# Audio.net
KiCad netlist of a schematic drawn in Altium Designer
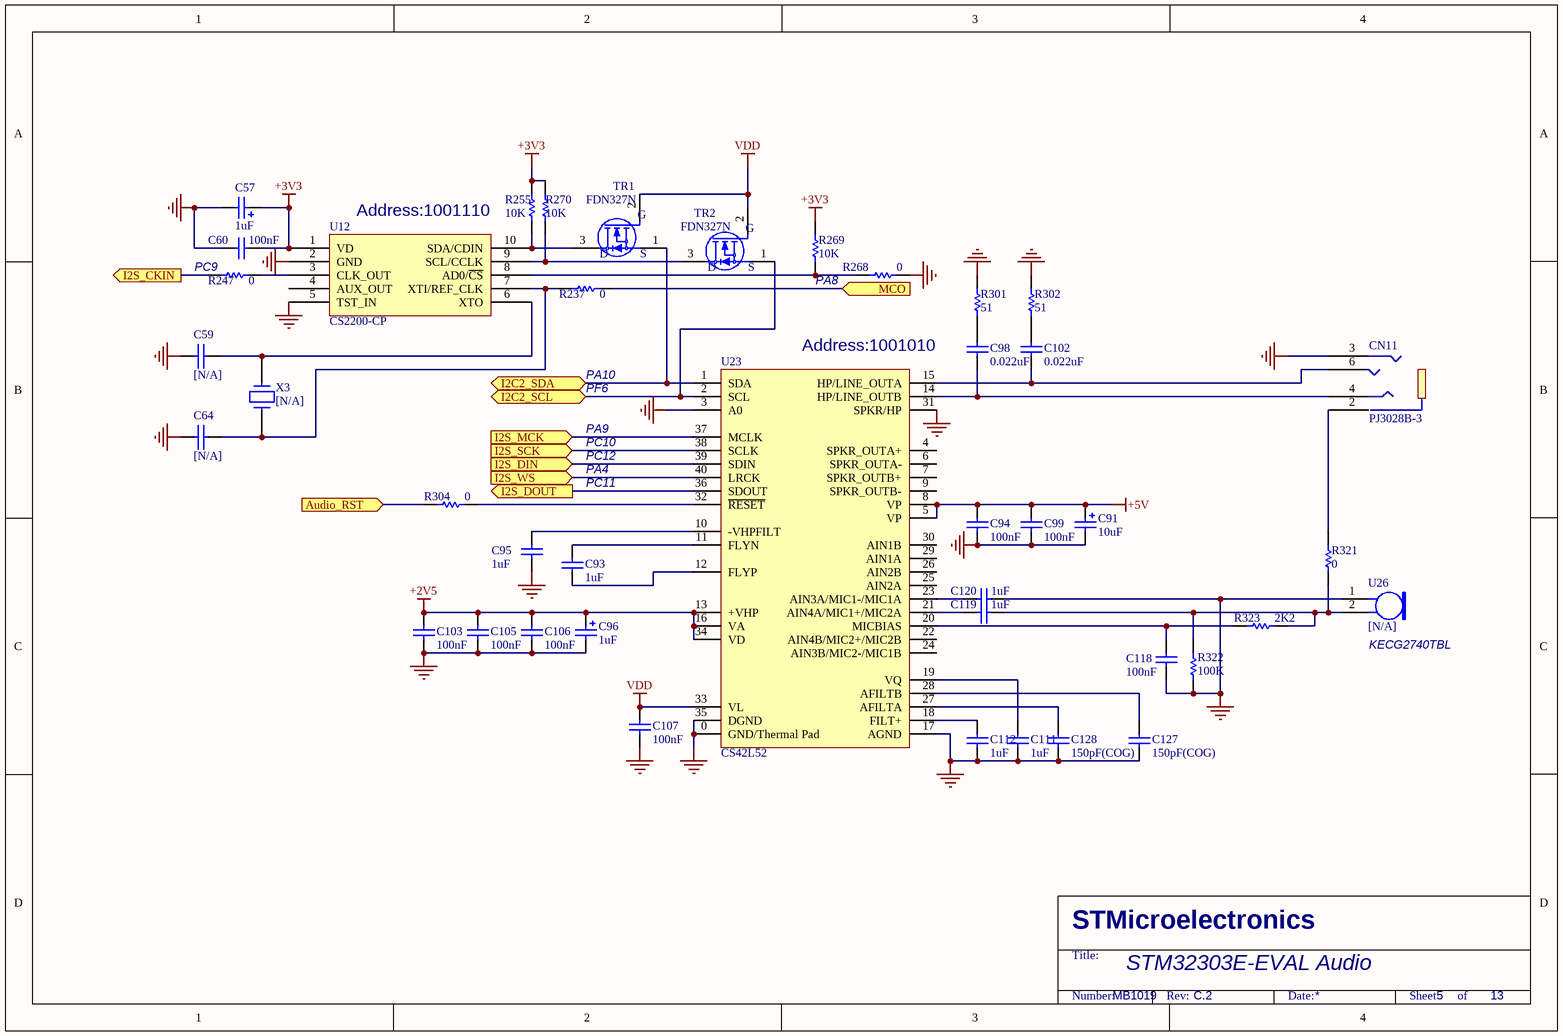
[diagram p0: Audio.SchDoc]

(export (version "E")
  (design (tool "Eeschema 10.0.6"))
  (components
    (comp (ref "C57")
      (value "1uF")
      (footprint "TAN-A")
      (description "Polarized Capacitor (Radial)")
      (fields (field (name "PUBLISHER") "Altium Limited"))
      (libsource (lib "Miscellaneous Devices") (part "Cap Pol1"))
    )
    (comp (ref "C59")
      (value "[N/A]")
      (footprint "0603C")
      (description "Capacitor")
      (libsource (lib "*") (part "CAP"))
    )
    (comp (ref "C60")
      (value "100nF")
      (footprint "0603C")
      (description "Capacitor")
      (fields (field (name "PUBLISHER") "Altium Limited"))
      (libsource (lib "Miscellaneous Devices") (part "CAP"))
    )
    (comp (ref "C64")
      (value "[N/A]")
      (footprint "0603C")
      (description "Capacitor")
      (libsource (lib "*") (part "CAP"))
    )
    (comp (ref "C91")
      (value "10uF")
      (footprint "TAN-A")
      (description "Polarized Capacitor (Radial)")
      (fields (field (name "PUBLISHER") "Altium Limited"))
      (libsource (lib "Miscellaneous Devices") (part "Cap Pol1"))
    )
    (comp (ref "C93")
      (value "1uF")
      (footprint "0603C")
      (description "Capacitor")
      (fields (field (name "PUBLISHER") "Altium Limited"))
      (libsource (lib "Miscellaneous Devices") (part "CAP"))
    )
    (comp (ref "C94")
      (value "100nF")
      (footprint "0603C")
      (description "Capacitor")
      (fields (field (name "PUBLISHER") "Altium Limited"))
      (libsource (lib "Miscellaneous Devices") (part "Cap"))
    )
    (comp (ref "C95")
      (value "1uF")
      (footprint "0603C")
      (description "Capacitor")
      (fields (field (name "PUBLISHER") "Altium Limited"))
      (libsource (lib "Miscellaneous Devices") (part "CAP"))
    )
    (comp (ref "C96")
      (value "1uF")
      (footprint "TAN-A")
      (description "Polarized Capacitor (Radial)")
      (fields (field (name "PUBLISHER") "Altium Limited"))
      (libsource (lib "Miscellaneous Devices") (part "Cap Pol1"))
    )
    (comp (ref "C98")
      (value "0.022uF")
      (footprint "0603C")
      (description "Capacitor")
      (fields (field (name "PUBLISHER") "Altium Limited"))
      (libsource (lib "Miscellaneous Devices") (part "CAP"))
    )
    (comp (ref "C99")
      (value "100nF")
      (footprint "0603C")
      (description "Capacitor")
      (fields (field (name "PUBLISHER") "Altium Limited"))
      (libsource (lib "Miscellaneous Devices") (part "Cap"))
    )
    (comp (ref "C102")
      (value "0.022uF")
      (footprint "0603C")
      (description "Capacitor")
      (fields (field (name "PUBLISHER") "Altium Limited"))
      (libsource (lib "Miscellaneous Devices") (part "CAP"))
    )
    (comp (ref "C103")
      (value "100nF")
      (footprint "0603C")
      (description "Capacitor")
      (fields (field (name "PUBLISHER") "Altium Limited"))
      (libsource (lib "Miscellaneous Devices") (part "Cap"))
    )
    (comp (ref "C105")
      (value "100nF")
      (footprint "0603C")
      (description "Capacitor")
      (fields (field (name "PUBLISHER") "Altium Limited"))
      (libsource (lib "Miscellaneous Devices") (part "Cap"))
    )
    (comp (ref "C106")
      (value "100nF")
      (footprint "0603C")
      (description "Capacitor")
      (fields (field (name "PUBLISHER") "Altium Limited"))
      (libsource (lib "Miscellaneous Devices") (part "Cap"))
    )
    (comp (ref "C107")
      (value "100nF")
      (footprint "0603C")
      (description "Capacitor")
      (fields (field (name "PUBLISHER") "Altium Limited"))
      (libsource (lib "Miscellaneous Devices") (part "Cap"))
    )
    (comp (ref "C111")
      (value "1uF")
      (footprint "0603C")
      (description "Capacitor")
      (fields (field (name "PUBLISHER") "Altium Limited"))
      (libsource (lib "Miscellaneous Devices") (part "CAP"))
    )
    (comp (ref "C112")
      (value "1uF")
      (footprint "0603C")
      (description "Capacitor")
      (fields (field (name "PUBLISHER") "Altium Limited"))
      (libsource (lib "Miscellaneous Devices") (part "CAP"))
    )
    (comp (ref "C118")
      (value "100nF")
      (footprint "0603C")
      (description "Capacitor")
      (fields (field (name "PUBLISHER") "Altium Limited"))
      (libsource (lib "Miscellaneous Devices") (part "Cap"))
    )
    (comp (ref "C119")
      (value "1uF")
      (footprint "0603C")
      (description "Capacitor")
      (fields (field (name "PUBLISHER") "Altium Limited"))
      (libsource (lib "Miscellaneous Devices") (part "CAP"))
    )
    (comp (ref "C120")
      (value "1uF")
      (footprint "0603C")
      (description "Capacitor")
      (fields (field (name "PUBLISHER") "Altium Limited"))
      (libsource (lib "Miscellaneous Devices") (part "CAP"))
    )
    (comp (ref "C127")
      (value "150pF(COG)")
      (footprint "0603C")
      (description "Capacitor")
      (fields (field (name "PUBLISHER") "Altium Limited"))
      (libsource (lib "Miscellaneous Devices") (part "CAP"))
    )
    (comp (ref "C128")
      (value "150pF(COG)")
      (footprint "0603C")
      (description "Capacitor")
      (fields (field (name "PUBLISHER") "Altium Limited"))
      (libsource (lib "Miscellaneous Devices") (part "CAP"))
    )
    (comp (ref "CN11") (value "PJ3028B-3") (footprint "PJ3028B") (libsource (lib "MB786") (part "PJ3028B-3")))
    (comp (ref "R237")
      (value "0")
      (footprint "0603R")
      (description "Resistor")
      (fields (field (name "PUBLISHER") "Altium Limited"))
      (libsource (lib "Miscellaneous Devices") (part "res1"))
    )
    (comp (ref "R247")
      (value "0")
      (footprint "0603R")
      (description "Resistor")
      (fields (field (name "PUBLISHER") "Altium Limited"))
      (libsource (lib "Miscellaneous Devices") (part "Res1"))
    )
    (comp (ref "R255")
      (value "10K")
      (footprint "0603R")
      (description "Resistor")
      (fields (field (name "PUBLISHER") "Altium Limited"))
      (libsource (lib "Miscellaneous Devices") (part "Res1"))
    )
    (comp (ref "R268")
      (value "0")
      (footprint "0603R")
      (description "Resistor")
      (fields (field (name "PUBLISHER") "Altium Limited"))
      (libsource (lib "Miscellaneous Devices") (part "res1"))
    )
    (comp (ref "R269")
      (value "10K")
      (footprint "0603R")
      (description "Resistor")
      (fields (field (name "PUBLISHER") "Altium Limited"))
      (libsource (lib "Miscellaneous Devices") (part "Res1"))
    )
    (comp (ref "R270")
      (value "10K")
      (footprint "0603R")
      (description "Resistor")
      (fields (field (name "PUBLISHER") "Altium Limited"))
      (libsource (lib "Miscellaneous Devices") (part "Res1"))
    )
    (comp (ref "R301")
      (value "51")
      (footprint "0603R")
      (description "Resistor")
      (fields (field (name "PUBLISHER") "Altium Limited"))
      (libsource (lib "Miscellaneous Devices") (part "res1"))
    )
    (comp (ref "R302")
      (value "51")
      (footprint "0603R")
      (description "Resistor")
      (fields (field (name "PUBLISHER") "Altium Limited"))
      (libsource (lib "Miscellaneous Devices") (part "res1"))
    )
    (comp (ref "R304")
      (value "0")
      (footprint "0603R")
      (description "Resistor")
      (fields (field (name "PUBLISHER") "Altium Limited"))
      (libsource (lib "Miscellaneous Devices") (part "Res1"))
    )
    (comp (ref "R321")
      (value "0")
      (footprint "0603R")
      (description "Resistor")
      (fields (field (name "PUBLISHER") "Altium Limited"))
      (libsource (lib "Miscellaneous Devices") (part "res1"))
    )
    (comp (ref "R322")
      (value "100K")
      (footprint "0603R")
      (description "Resistor")
      (fields (field (name "PUBLISHER") "Altium Limited"))
      (libsource (lib "Miscellaneous Devices") (part "res1"))
    )
    (comp (ref "R323")
      (value "2K2")
      (footprint "0603R")
      (description "Resistor")
      (fields (field (name "PUBLISHER") "Altium Limited"))
      (libsource (lib "Miscellaneous Devices") (part "Res1"))
    )
    (comp (ref "TR1") (value "FDN327N") (footprint "SOT-23") (libsource (lib "MB525") (part "2N7000")))
    (comp (ref "TR2") (value "FDN327N") (footprint "SOT-23") (libsource (lib "MB525") (part "2N7000")))
    (comp (ref "U12")
      (value "CS2200-CP")
      (footprint "MSOP10(0.5)")
      (libsource (lib "MB786") (part "CS2200-CP"))
    )
    (comp (ref "U23") (value "CS42L52") (footprint "QFN40(6*6)") (libsource (lib "MB1019") (part "CS42L52")))
    (comp (ref "U26")
      (value "[N/A]")
      (footprint "KEC2740")
      (description "Microphone")
      (fields (field (name "PUBLISHER") "Altium Limited"))
      (libsource (lib "Miscellaneous Devices") (part "Mic2"))
    )
    (comp (ref "X3")
      (value "[N/A]")
      (footprint "XTAL_socket")
      (description "Crystal")
      (libsource (lib "*") (part "CRYSTAL"))
    )
  )
  (nets
    (net (code "1") (name "+2V5") (class "Default")
      (node (ref "C103") (pin "1") (pinfunction "1_1") (pintype "passive"))
      (node (ref "C105") (pin "1") (pinfunction "1_1") (pintype "passive"))
      (node (ref "C106") (pin "1") (pinfunction "1_1") (pintype "passive"))
      (node (ref "C96") (pin "1") (pinfunction "1_1") (pintype "passive"))
      (node (ref "U23") (pin "13") (pinfunction "+VHP_13") (pintype "passive"))
      (node (ref "U23") (pin "16") (pinfunction "VA_16") (pintype "passive"))
      (node (ref "U23") (pin "34") (pinfunction "VD_34") (pintype "passive"))
    )
    (net (code "2") (name "+3V3") (class "Default")
      (node (ref "C57") (pin "1") (pinfunction "1_1") (pintype "passive"))
      (node (ref "C60") (pin "1") (pinfunction "1_1") (pintype "passive"))
      (node (ref "R255") (pin "1") (pinfunction "1_1") (pintype "passive"))
      (node (ref "R269") (pin "1") (pinfunction "1_1") (pintype "passive"))
      (node (ref "R270") (pin "1") (pinfunction "1_1") (pintype "passive"))
      (node (ref "U12") (pin "1") (pinfunction "VD_1") (pintype "passive"))
    )
    (net (code "3") (name "+5V") (class "Default")
      (node (ref "C91") (pin "1") (pinfunction "1_1") (pintype "passive"))
      (node (ref "C94") (pin "1") (pinfunction "1_1") (pintype "passive"))
      (node (ref "C99") (pin "1") (pinfunction "1_1") (pintype "passive"))
      (node (ref "U23") (pin "5") (pinfunction "VP_5") (pintype "passive"))
      (node (ref "U23") (pin "8") (pinfunction "VP_8") (pintype "passive"))
    )
    (net (code "4") (name "/Audio_RST") (class "Default")
      (node (ref "R304") (pin "2") (pinfunction "2_2") (pintype "passive"))
    )
    (net (code "5") (name "/I2C2_SCL") (class "Default")
      (node (ref "TR2") (pin "1") (pinfunction "S_1") (pintype "passive"))
      (node (ref "U23") (pin "2") (pinfunction "SCL_2") (pintype "passive"))
    )
    (net (code "6") (name "/I2C2_SDA") (class "Default")
      (node (ref "TR1") (pin "1") (pinfunction "S_1") (pintype "passive"))
      (node (ref "U23") (pin "1") (pinfunction "SDA_1") (pintype "passive"))
    )
    (net (code "7") (name "/I2S_CKIN") (class "Default")
      (node (ref "R247") (pin "2") (pinfunction "2_2") (pintype "passive"))
    )
    (net (code "8") (name "/I2S_DIN") (class "Default")
      (node (ref "U23") (pin "39") (pinfunction "SDIN_39") (pintype "passive"))
    )
    (net (code "9") (name "/I2S_DOUT") (class "Default")
      (node (ref "U23") (pin "36") (pinfunction "SDOUT_36") (pintype "passive"))
    )
    (net (code "10") (name "/I2S_MCK") (class "Default")
      (node (ref "U23") (pin "37") (pinfunction "MCLK_37") (pintype "passive"))
    )
    (net (code "11") (name "/I2S_SCK") (class "Default")
      (node (ref "U23") (pin "38") (pinfunction "SCLK_38") (pintype "passive"))
    )
    (net (code "12") (name "/I2S_WS") (class "Default")
      (node (ref "U23") (pin "40") (pinfunction "LRCK_40") (pintype "passive"))
    )
    (net (code "13") (name "/MCO") (class "Default")
      (node (ref "R237") (pin "1") (pinfunction "1_1") (pintype "passive"))
    )
    (net (code "14") (name "GND") (class "Default")
      (node (ref "C103") (pin "2") (pinfunction "2_2") (pintype "passive"))
      (node (ref "C105") (pin "2") (pinfunction "2_2") (pintype "passive"))
      (node (ref "C106") (pin "2") (pinfunction "2_2") (pintype "passive"))
      (node (ref "C107") (pin "2") (pinfunction "2_2") (pintype "passive"))
      (node (ref "C111") (pin "1") (pinfunction "1_1") (pintype "passive"))
      (node (ref "C112") (pin "1") (pinfunction "1_1") (pintype "passive"))
      (node (ref "C118") (pin "2") (pinfunction "2_2") (pintype "passive"))
      (node (ref "C120") (pin "2") (pinfunction "2_2") (pintype "passive"))
      (node (ref "C127") (pin "1") (pinfunction "1_1") (pintype "passive"))
      (node (ref "C128") (pin "1") (pinfunction "1_1") (pintype "passive"))
      (node (ref "C57") (pin "2") (pinfunction "2_2") (pintype "passive"))
      (node (ref "C59") (pin "2") (pinfunction "2_2") (pintype "passive"))
      (node (ref "C60") (pin "2") (pinfunction "2_2") (pintype "passive"))
      (node (ref "C64") (pin "2") (pinfunction "2_2") (pintype "passive"))
      (node (ref "C91") (pin "2") (pinfunction "2_2") (pintype "passive"))
      (node (ref "C94") (pin "2") (pinfunction "2_2") (pintype "passive"))
      (node (ref "C95") (pin "2") (pinfunction "2_2") (pintype "passive"))
      (node (ref "C96") (pin "2") (pinfunction "2_2") (pintype "passive"))
      (node (ref "C99") (pin "2") (pinfunction "2_2") (pintype "passive"))
      (node (ref "CN11") (pin "3") (pintype "passive"))
      (node (ref "R268") (pin "1") (pinfunction "1_1") (pintype "passive"))
      (node (ref "R301") (pin "1") (pinfunction "1_1") (pintype "passive"))
      (node (ref "R302") (pin "1") (pinfunction "1_1") (pintype "passive"))
      (node (ref "R322") (pin "2") (pinfunction "2_2") (pintype "passive"))
      (node (ref "U12") (pin "2") (pinfunction "GND_2") (pintype "passive"))
      (node (ref "U12") (pin "5") (pinfunction "TST_IN_5") (pintype "passive"))
      (node (ref "U23") (pin "0") (pinfunction "GND/Thermal_Pad_0") (pintype "passive"))
      (node (ref "U23") (pin "17") (pinfunction "AGND_17") (pintype "passive"))
      (node (ref "U23") (pin "3") (pinfunction "A0_3") (pintype "passive"))
      (node (ref "U23") (pin "31") (pinfunction "SPKR/HP_31") (pintype "passive"))
      (node (ref "U23") (pin "35") (pinfunction "DGND_35") (pintype "passive"))
      (node (ref "U26") (pin "1") (pinfunction "1_1") (pintype "passive"))
    )
    (net (code "15") (name "Net-(C98-Pad1)") (class "Default")
      (node (ref "C98") (pin "1") (pinfunction "1_1") (pintype "passive"))
      (node (ref "R301") (pin "2") (pinfunction "2_2") (pintype "passive"))
    )
    (net (code "16") (name "Net-(C102-Pad1)") (class "Default")
      (node (ref "C102") (pin "1") (pinfunction "1_1") (pintype "passive"))
      (node (ref "R302") (pin "2") (pinfunction "2_2") (pintype "passive"))
    )
    (net (code "17") (name "Net-(C119-Pad2)") (class "Default")
      (node (ref "C119") (pin "2") (pinfunction "2_2") (pintype "passive"))
      (node (ref "R321") (pin "1") (pinfunction "1_1") (pintype "passive"))
      (node (ref "R322") (pin "1") (pinfunction "1_1") (pintype "passive"))
      (node (ref "R323") (pin "1") (pinfunction "1_1") (pintype "passive"))
      (node (ref "U26") (pin "2") (pinfunction "2_2") (pintype "passive"))
    )
    (net (code "18") (name "Net-(CN11-Pad2)") (class "Default")
      (node (ref "CN11") (pin "2") (pintype "passive"))
      (node (ref "R321") (pin "2") (pinfunction "2_2") (pintype "passive"))
    )
    (net (code "19") (name "Net-(TR1-D)") (class "Default")
      (node (ref "R255") (pin "2") (pinfunction "2_2") (pintype "passive"))
      (node (ref "TR1") (pin "3") (pinfunction "D_3") (pintype "passive"))
      (node (ref "U12") (pin "10") (pinfunction "SDA/CDIN_10") (pintype "passive"))
    )
    (net (code "20") (name "Net-(TR2-D)") (class "Default")
      (node (ref "R270") (pin "2") (pinfunction "2_2") (pintype "passive"))
      (node (ref "TR2") (pin "3") (pinfunction "D_3") (pintype "passive"))
      (node (ref "U12") (pin "9") (pinfunction "SCL/CCLK_9") (pintype "passive"))
    )
    (net (code "21") (name "Net-(U12-AD0{slash}~{CS})") (class "Default")
      (node (ref "R268") (pin "2") (pinfunction "2_2") (pintype "passive"))
      (node (ref "R269") (pin "2") (pinfunction "2_2") (pintype "passive"))
      (node (ref "U12") (pin "8") (pinfunction "AD0/~{CS}_8") (pintype "passive"))
    )
    (net (code "22") (name "Net-(U12-CLK_OUT)") (class "Default")
      (node (ref "R247") (pin "1") (pinfunction "1_1") (pintype "passive"))
      (node (ref "U12") (pin "3") (pinfunction "CLK_OUT_3") (pintype "passive"))
    )
    (net (code "23") (name "Net-(U12-XTI{slash}REF_CLK)") (class "Default")
      (node (ref "C64") (pin "1") (pinfunction "1_1") (pintype "passive"))
      (node (ref "R237") (pin "2") (pinfunction "2_2") (pintype "passive"))
      (node (ref "U12") (pin "7") (pinfunction "XTI/REF_CLK_7") (pintype "passive"))
      (node (ref "X3") (pin "1") (pinfunction "1_1") (pintype "passive"))
    )
    (net (code "24") (name "Net-(U12-XTO)") (class "Default")
      (node (ref "C59") (pin "1") (pinfunction "1_1") (pintype "passive"))
      (node (ref "U12") (pin "6") (pinfunction "XTO_6") (pintype "passive"))
      (node (ref "X3") (pin "2") (pinfunction "2_2") (pintype "passive"))
    )
    (net (code "25") (name "Net-(U23--VHPFILT)") (class "Default")
      (node (ref "C95") (pin "1") (pinfunction "1_1") (pintype "passive"))
      (node (ref "U23") (pin "10") (pinfunction "-VHPFILT_10") (pintype "passive"))
    )
    (net (code "26") (name "Net-(U23-AFILTA)") (class "Default")
      (node (ref "C128") (pin "2") (pinfunction "2_2") (pintype "passive"))
      (node (ref "U23") (pin "27") (pinfunction "AFILTA_27") (pintype "passive"))
    )
    (net (code "27") (name "Net-(U23-AFILTB)") (class "Default")
      (node (ref "C127") (pin "2") (pinfunction "2_2") (pintype "passive"))
      (node (ref "U23") (pin "28") (pinfunction "AFILTB_28") (pintype "passive"))
    )
    (net (code "28") (name "Net-(U23-AIN3A{slash}MIC1-{slash}MIC1A)") (class "Default")
      (node (ref "C120") (pin "1") (pinfunction "1_1") (pintype "passive"))
      (node (ref "U23") (pin "23") (pinfunction "AIN3A/MIC1-/MIC1A_23") (pintype "passive"))
    )
    (net (code "29") (name "Net-(U23-AIN4A{slash}MIC1+{slash}MIC2A)") (class "Default")
      (node (ref "C119") (pin "1") (pinfunction "1_1") (pintype "passive"))
      (node (ref "U23") (pin "21") (pinfunction "AIN4A/MIC1+/MIC2A_21") (pintype "passive"))
    )
    (net (code "30") (name "Net-(U23-FILT+)") (class "Default")
      (node (ref "C112") (pin "2") (pinfunction "2_2") (pintype "passive"))
      (node (ref "U23") (pin "18") (pinfunction "FILT+_18") (pintype "passive"))
    )
    (net (code "31") (name "Net-(U23-FLYN)") (class "Default")
      (node (ref "C93") (pin "2") (pinfunction "2_2") (pintype "passive"))
      (node (ref "U23") (pin "11") (pinfunction "FLYN_11") (pintype "passive"))
    )
    (net (code "32") (name "Net-(U23-FLYP)") (class "Default")
      (node (ref "C93") (pin "1") (pinfunction "1_1") (pintype "passive"))
      (node (ref "U23") (pin "12") (pinfunction "FLYP_12") (pintype "passive"))
    )
    (net (code "33") (name "Net-(U23-HP{slash}LINE_OUTA)") (class "Default")
      (node (ref "C102") (pin "2") (pinfunction "2_2") (pintype "passive"))
      (node (ref "CN11") (pin "6") (pintype "passive"))
      (node (ref "U23") (pin "15") (pinfunction "HP/LINE_OUTA_15") (pintype "passive"))
    )
    (net (code "34") (name "Net-(U23-HP{slash}LINE_OUTB)") (class "Default")
      (node (ref "C98") (pin "2") (pinfunction "2_2") (pintype "passive"))
      (node (ref "CN11") (pin "4") (pintype "passive"))
      (node (ref "U23") (pin "14") (pinfunction "HP/LINE_OUTB_14") (pintype "passive"))
    )
    (net (code "35") (name "Net-(U23-MICBIAS)") (class "Default")
      (node (ref "C118") (pin "1") (pinfunction "1_1") (pintype "passive"))
      (node (ref "R323") (pin "2") (pinfunction "2_2") (pintype "passive"))
      (node (ref "U23") (pin "20") (pinfunction "MICBIAS_20") (pintype "passive"))
    )
    (net (code "36") (name "Net-(U23-VQ)") (class "Default")
      (node (ref "C111") (pin "2") (pinfunction "2_2") (pintype "passive"))
      (node (ref "U23") (pin "19") (pinfunction "VQ_19") (pintype "passive"))
    )
    (net (code "37") (name "Net-(U23-~{RESET})") (class "Default")
      (node (ref "R304") (pin "1") (pinfunction "1_1") (pintype "passive"))
      (node (ref "U23") (pin "32") (pinfunction "~{RESET}_32") (pintype "passive"))
    )
    (net (code "38") (name "VDD") (class "Default")
      (node (ref "C107") (pin "1") (pinfunction "1_1") (pintype "passive"))
      (node (ref "TR1") (pin "2") (pinfunction "G_2") (pintype "passive"))
      (node (ref "TR2") (pin "2") (pinfunction "G_2") (pintype "passive"))
      (node (ref "U23") (pin "33") (pinfunction "VL_33") (pintype "passive"))
    )
    (net (code "39") (name "unconnected-(U12-AUX_OUT-Pad4)") (class "Default")
      (node (ref "U12") (pin "4") (pinfunction "AUX_OUT_4") (pintype "passive"))
    )
    (net (code "40") (name "unconnected-(U23-AIN1A-Pad29)") (class "Default")
      (node (ref "U23") (pin "29") (pinfunction "AIN1A_29") (pintype "passive"))
    )
    (net (code "41") (name "unconnected-(U23-AIN1B-Pad30)") (class "Default")
      (node (ref "U23") (pin "30") (pinfunction "AIN1B_30") (pintype "passive"))
    )
    (net (code "42") (name "unconnected-(U23-AIN2A-Pad25)") (class "Default")
      (node (ref "U23") (pin "25") (pinfunction "AIN2A_25") (pintype "passive"))
    )
    (net (code "43") (name "unconnected-(U23-AIN2B-Pad26)") (class "Default")
      (node (ref "U23") (pin "26") (pinfunction "AIN2B_26") (pintype "passive"))
    )
    (net (code "44") (name "unconnected-(U23-AIN3B{slash}MIC2-{slash}MIC1B-Pad24)") (class "Default")
      (node (ref "U23") (pin "24") (pinfunction "AIN3B/MIC2-/MIC1B_24") (pintype "passive"))
    )
    (net (code "45") (name "unconnected-(U23-AIN4B{slash}MIC2+{slash}MIC2B-Pad22)") (class "Default")
      (node (ref "U23") (pin "22") (pinfunction "AIN4B/MIC2+/MIC2B_22") (pintype "passive"))
    )
    (net (code "46") (name "unconnected-(U23-SPKR_OUTA+-Pad4)") (class "Default")
      (node (ref "U23") (pin "4") (pinfunction "SPKR_OUTA+_4") (pintype "passive"))
    )
    (net (code "47") (name "unconnected-(U23-SPKR_OUTA--Pad6)") (class "Default")
      (node (ref "U23") (pin "6") (pinfunction "SPKR_OUTA-_6") (pintype "passive"))
    )
    (net (code "48") (name "unconnected-(U23-SPKR_OUTB+-Pad7)") (class "Default")
      (node (ref "U23") (pin "7") (pinfunction "SPKR_OUTB+_7") (pintype "passive"))
    )
    (net (code "49") (name "unconnected-(U23-SPKR_OUTB--Pad9)") (class "Default")
      (node (ref "U23") (pin "9") (pinfunction "SPKR_OUTB-_9") (pintype "passive"))
    )
  )
)
